# OpenLaser.net
KiCad netlist of a schematic drawn in Altium Designer
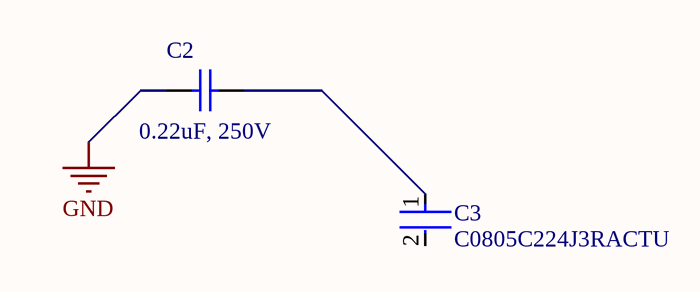
[diagram p0: OpenLaser.SchDoc]

(export (version "E")
  (design (tool "Eeschema 10.0.6"))
  (components
    (comp (ref "C2")
      (value "0.22uF, 250V")
      (footprint "WCAP-FTBE_L10.5W6H12")
      (description "Cap, 0.22Uf, 250V, Film, Radial Rohs Compliant: Yes")
      (libsource (lib "Altium Content Vault") (part "Capacitor_Non-Polarized"))
    )
    (comp (ref "C3")
      (value "C0805C224J3RACTU")
      (footprint "FP-C0805C-DN-MFG")
      (description "C0805 0.22 μF X7R 30ppm/°C 5.00% 25 V")
      (fields (field (name "TOLERANCE") "0.05"))
      (libsource (lib "Altium Content Vault") (part "b4654b650e69147ec39a6b967a45e02"))
    )
  )
  (nets
    (net (code "1") (name "GND") (class "Default")
      (node (ref "C2") (pin "1") (pinfunction "1_1") (pintype "passive"))
    )
    (net (code "2") (name "Net-(C2-Pad2)") (class "Default")
      (node (ref "C2") (pin "2") (pinfunction "2_2") (pintype "passive"))
      (node (ref "C3") (pin "1") (pinfunction "1_1") (pintype "passive"))
    )
    (net (code "3") (name "unconnected-(C3-Pad2)") (class "Default")
      (node (ref "C3") (pin "2") (pinfunction "2_2") (pintype "passive"))
    )
  )
)
